# Modulo_de_expansao.net
KiCad netlist of a schematic drawn in EAGLE
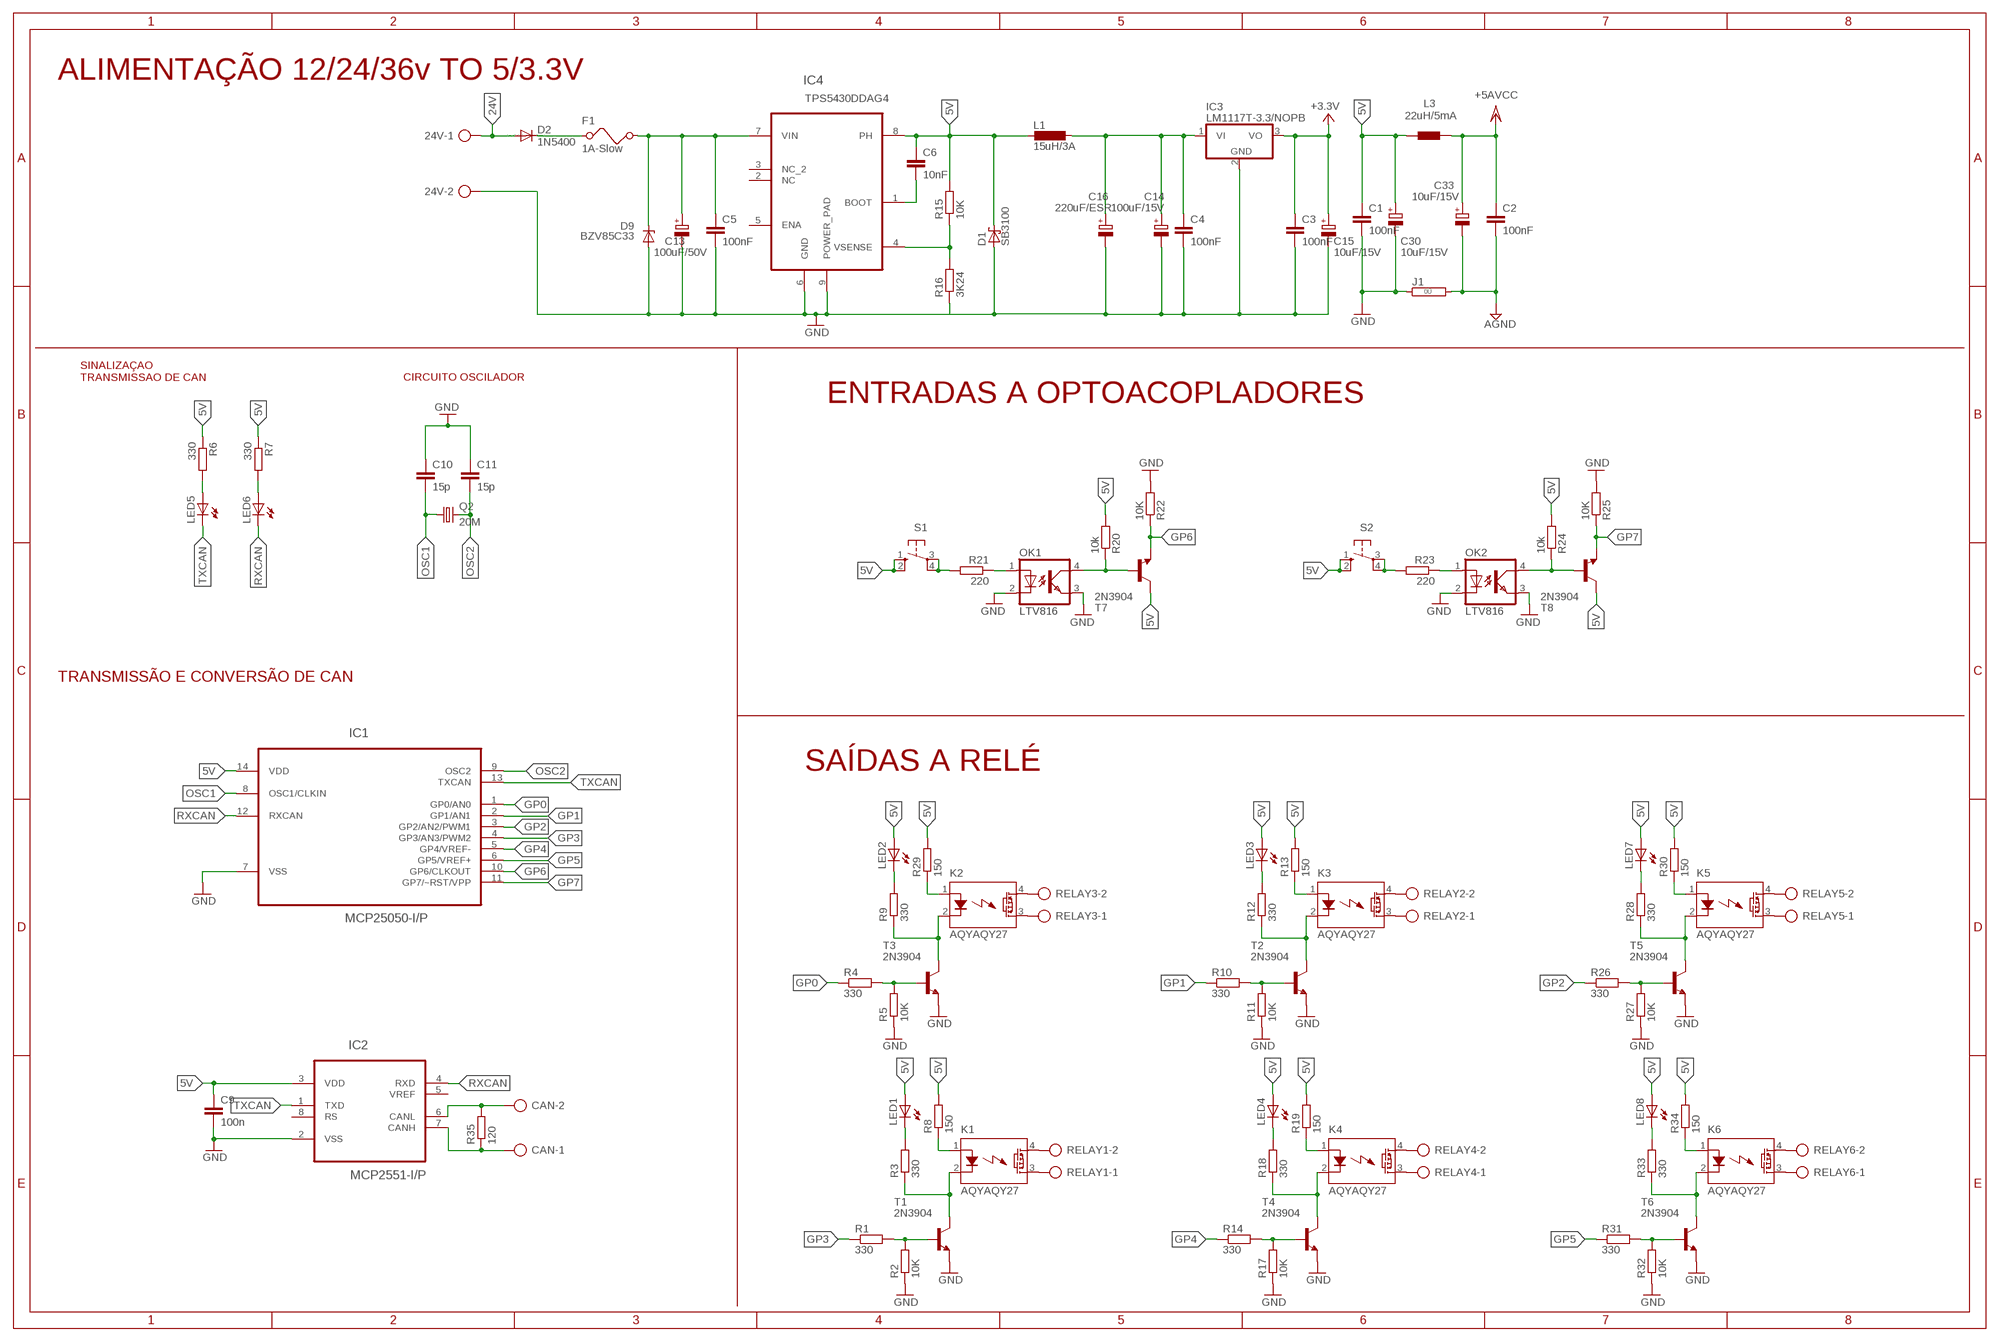
[diagram p0: schematic, sheet 1]

(export (version "E")
  (design (tool "Eeschema 10.0.6"))
  (components
    (comp (ref "24V")
      (value "AK300/2")
      (footprint "eagle-import:AK300_2")
      (libsource (lib "eagle-import") (part "AK300/2"))
    )
    (comp (ref "C1")
      (value "100nF")
      (footprint "eagle-import:C050-024X044")
      (libsource (lib "eagle-import") (part "C-EU050-024X044"))
    )
    (comp (ref "C2")
      (value "100nF")
      (footprint "eagle-import:C050-024X044")
      (libsource (lib "eagle-import") (part "C-EU050-024X044"))
    )
    (comp (ref "C3")
      (value "100nF")
      (footprint "eagle-import:C050-024X044")
      (libsource (lib "eagle-import") (part "C-EU050-024X044"))
    )
    (comp (ref "C4")
      (value "100nF")
      (footprint "eagle-import:C050-024X044")
      (libsource (lib "eagle-import") (part "C-EU050-024X044"))
    )
    (comp (ref "C5")
      (value "100nF")
      (footprint "eagle-import:C050-024X044")
      (libsource (lib "eagle-import") (part "C-EU050-024X044"))
    )
    (comp (ref "C6")
      (value "10nF")
      (footprint "eagle-import:C075-032X103")
      (libsource (lib "eagle-import") (part "C-EU075-032X103"))
    )
    (comp (ref "C9")
      (value "100n")
      (footprint "eagle-import:C050-025X075")
      (libsource (lib "eagle-import") (part "C-EU050-025X075"))
    )
    (comp (ref "C10")
      (value "15p")
      (footprint "eagle-import:C025-024X044")
      (libsource (lib "eagle-import") (part "C-EU025-024X044"))
    )
    (comp (ref "C11")
      (value "15p")
      (footprint "eagle-import:C025-024X044")
      (libsource (lib "eagle-import") (part "C-EU025-024X044"))
    )
    (comp (ref "C13")
      (value "100uF/50V")
      (footprint "eagle-import:E5-10,5")
      (libsource (lib "eagle-import") (part "CPOL-EUE5-10.5"))
    )
    (comp (ref "C14")
      (value "100uF/15V")
      (footprint "eagle-import:E5-10,5")
      (libsource (lib "eagle-import") (part "CPOL-EUE5-10.5"))
    )
    (comp (ref "C15")
      (value "10uF/15V")
      (footprint "eagle-import:E5-10,5")
      (libsource (lib "eagle-import") (part "CPOL-EUE5-10.5"))
    )
    (comp (ref "C16")
      (value "220uF/ESR")
      (footprint "eagle-import:E5-10,5")
      (libsource (lib "eagle-import") (part "CPOL-EUE5-10.5"))
    )
    (comp (ref "C30")
      (value "10uF/15V")
      (footprint "eagle-import:E5-10,5")
      (libsource (lib "eagle-import") (part "CPOL-EUE5-10.5"))
    )
    (comp (ref "C33")
      (value "10uF/15V")
      (footprint "eagle-import:E5-10,5")
      (libsource (lib "eagle-import") (part "CPOL-EUE5-10.5"))
    )
    (comp (ref "CAN")
      (value "AK300/2")
      (footprint "eagle-import:AK300_2")
      (libsource (lib "eagle-import") (part "AK300/2"))
    )
    (comp (ref "D1")
      (value "SB3100")
      (footprint "eagle-import:C4111-15")
      (libsource (lib "eagle-import") (part "1N5908"))
    )
    (comp (ref "D2")
      (value "1N5400")
      (footprint "eagle-import:DO201-15")
      (libsource (lib "eagle-import") (part "1N5400"))
    )
    (comp (ref "D9")
      (value "BZV85C33")
      (footprint "eagle-import:F126Z10")
      (libsource (lib "eagle-import") (part "ZENER-DIODEF126-10"))
    )
    (comp (ref "F1")
      (value "1A-Slow")
      (footprint "eagle-import:FUSE")
      (libsource (lib "eagle-import") (part "FUSE"))
    )
    (comp (ref "IC1")
      (value "MCP25050-I/P")
      (footprint "eagle-import:DIP254P762X432-14")
      (libsource (lib "eagle-import") (part "MCP25050-I/P"))
    )
    (comp (ref "IC2")
      (value "MCP2551-I/P")
      (footprint "eagle-import:DIP254P762X432-8")
      (libsource (lib "eagle-import") (part "MCP2551-I/P"))
    )
    (comp (ref "IC3")
      (value "LM1117T-3.3/NOPB")
      (footprint "eagle-import:TO220H")
      (libsource (lib "eagle-import") (part "LM340?-H12"))
    )
    (comp (ref "IC4")
      (value "TPS5430DDAG4")
      (footprint "eagle-import:SOIC127P600X170-9N")
      (fields (field (name "MPN") "TPS5430DDAG4"))
      (libsource (lib "eagle-import") (part "TPS5430DDAG4"))
    )
    (comp (ref "J1")
      (value "0R")
      (footprint "eagle-import:0R_10")
      (libsource (lib "eagle-import") (part "0R"))
    )
    (comp (ref "K1")
      (value "AQYAQY27")
      (footprint "eagle-import:AQY27")
      (libsource (lib "eagle-import") (part "AQYAQY27"))
    )
    (comp (ref "K2")
      (value "AQYAQY27")
      (footprint "eagle-import:AQY27")
      (libsource (lib "eagle-import") (part "AQYAQY27"))
    )
    (comp (ref "K3")
      (value "AQYAQY27")
      (footprint "eagle-import:AQY27")
      (libsource (lib "eagle-import") (part "AQYAQY27"))
    )
    (comp (ref "K4")
      (value "AQYAQY27")
      (footprint "eagle-import:AQY27")
      (libsource (lib "eagle-import") (part "AQYAQY27"))
    )
    (comp (ref "K5")
      (value "AQYAQY27")
      (footprint "eagle-import:AQY27")
      (libsource (lib "eagle-import") (part "AQYAQY27"))
    )
    (comp (ref "K6")
      (value "AQYAQY27")
      (footprint "eagle-import:AQY27")
      (libsource (lib "eagle-import") (part "AQYAQY27"))
    )
    (comp (ref "L1")
      (value "15uH/3A")
      (footprint "eagle-import:TJ3-U1")
      (libsource (lib "eagle-import") (part "L-EUTJ3-U1"))
    )
    (comp (ref "L3")
      (value "22uH/5mA")
      (footprint "eagle-import:BL01RN1A")
      (libsource (lib "eagle-import") (part "BL01RN1A"))
    )
    (comp (ref "LED1")
      (value "LED3MM")
      (footprint "eagle-import:LED3MM")
      (libsource (lib "eagle-import") (part "LED3MM"))
    )
    (comp (ref "LED2")
      (value "LED3MM")
      (footprint "eagle-import:LED3MM")
      (libsource (lib "eagle-import") (part "LED3MM"))
    )
    (comp (ref "LED3")
      (value "LED3MM")
      (footprint "eagle-import:LED3MM")
      (libsource (lib "eagle-import") (part "LED3MM"))
    )
    (comp (ref "LED4")
      (value "LED3MM")
      (footprint "eagle-import:LED3MM")
      (libsource (lib "eagle-import") (part "LED3MM"))
    )
    (comp (ref "LED5")
      (value "LED3MM")
      (footprint "eagle-import:LED3MM")
      (libsource (lib "eagle-import") (part "LED3MM"))
    )
    (comp (ref "LED6")
      (value "LED3MM")
      (footprint "eagle-import:LED3MM")
      (libsource (lib "eagle-import") (part "LED3MM"))
    )
    (comp (ref "LED7")
      (value "LED3MM")
      (footprint "eagle-import:LED3MM")
      (libsource (lib "eagle-import") (part "LED3MM"))
    )
    (comp (ref "LED8")
      (value "LED3MM")
      (footprint "eagle-import:LED3MM")
      (libsource (lib "eagle-import") (part "LED3MM"))
    )
    (comp (ref "OK1")
      (value "LTV816")
      (footprint "eagle-import:DIL04")
      (libsource (lib "eagle-import") (part "LTV816"))
    )
    (comp (ref "OK2")
      (value "LTV816")
      (footprint "eagle-import:DIL04")
      (libsource (lib "eagle-import") (part "LTV816"))
    )
    (comp (ref "Q2")
      (value "20M")
      (footprint "eagle-import:HC49_S")
      (libsource (lib "eagle-import") (part "CRYSTALHC49S"))
    )
    (comp (ref "R1")
      (value "330")
      (footprint "eagle-import:0204_5")
      (libsource (lib "eagle-import") (part "R-EU_0204/5"))
    )
    (comp (ref "R2")
      (value "10K")
      (footprint "eagle-import:0204_5")
      (libsource (lib "eagle-import") (part "R-EU_0204/5"))
    )
    (comp (ref "R3")
      (value "330")
      (footprint "eagle-import:0204_5")
      (libsource (lib "eagle-import") (part "R-EU_0204/5"))
    )
    (comp (ref "R4")
      (value "330")
      (footprint "eagle-import:0204_5")
      (libsource (lib "eagle-import") (part "R-EU_0204/5"))
    )
    (comp (ref "R5")
      (value "10K")
      (footprint "eagle-import:0204_5")
      (libsource (lib "eagle-import") (part "R-EU_0204/5"))
    )
    (comp (ref "R6")
      (value "330")
      (footprint "eagle-import:0204_5")
      (libsource (lib "eagle-import") (part "R-EU_0204/5"))
    )
    (comp (ref "R7")
      (value "330")
      (footprint "eagle-import:0204_5")
      (libsource (lib "eagle-import") (part "R-EU_0204/5"))
    )
    (comp (ref "R8")
      (value "150")
      (footprint "eagle-import:0204_5")
      (libsource (lib "eagle-import") (part "R-EU_0204/5"))
    )
    (comp (ref "R9")
      (value "330")
      (footprint "eagle-import:0204_5")
      (libsource (lib "eagle-import") (part "R-EU_0204/5"))
    )
    (comp (ref "R10")
      (value "330")
      (footprint "eagle-import:0204_5")
      (libsource (lib "eagle-import") (part "R-EU_0204/5"))
    )
    (comp (ref "R11")
      (value "10K")
      (footprint "eagle-import:0204_5")
      (libsource (lib "eagle-import") (part "R-EU_0204/5"))
    )
    (comp (ref "R12")
      (value "330")
      (footprint "eagle-import:0204_5")
      (libsource (lib "eagle-import") (part "R-EU_0204/5"))
    )
    (comp (ref "R13")
      (value "150")
      (footprint "eagle-import:0204_5")
      (libsource (lib "eagle-import") (part "R-EU_0204/5"))
    )
    (comp (ref "R14")
      (value "330")
      (footprint "eagle-import:0204_5")
      (libsource (lib "eagle-import") (part "R-EU_0204/5"))
    )
    (comp (ref "R15")
      (value "10K")
      (footprint "eagle-import:0204_7")
      (libsource (lib "eagle-import") (part "R-EU_0204/7"))
    )
    (comp (ref "R16")
      (value "3K24")
      (footprint "eagle-import:0204_7")
      (libsource (lib "eagle-import") (part "R-EU_0204/7"))
    )
    (comp (ref "R17")
      (value "10K")
      (footprint "eagle-import:0204_5")
      (libsource (lib "eagle-import") (part "R-EU_0204/5"))
    )
    (comp (ref "R18")
      (value "330")
      (footprint "eagle-import:0204_5")
      (libsource (lib "eagle-import") (part "R-EU_0204/5"))
    )
    (comp (ref "R19")
      (value "150")
      (footprint "eagle-import:0204_5")
      (libsource (lib "eagle-import") (part "R-EU_0204/5"))
    )
    (comp (ref "R20")
      (value "10k")
      (footprint "eagle-import:0204_5")
      (libsource (lib "eagle-import") (part "R-EU_0204/5"))
    )
    (comp (ref "R21")
      (value "220")
      (footprint "eagle-import:0204_5")
      (libsource (lib "eagle-import") (part "R-EU_0204/5"))
    )
    (comp (ref "R22")
      (value "10K")
      (footprint "eagle-import:0204_5")
      (libsource (lib "eagle-import") (part "R-EU_0204/5"))
    )
    (comp (ref "R23")
      (value "220")
      (footprint "eagle-import:0204_5")
      (libsource (lib "eagle-import") (part "R-EU_0204/5"))
    )
    (comp (ref "R24")
      (value "10k")
      (footprint "eagle-import:0204_5")
      (libsource (lib "eagle-import") (part "R-EU_0204/5"))
    )
    (comp (ref "R25")
      (value "10K")
      (footprint "eagle-import:0204_5")
      (libsource (lib "eagle-import") (part "R-EU_0204/5"))
    )
    (comp (ref "R26")
      (value "330")
      (footprint "eagle-import:0204_5")
      (libsource (lib "eagle-import") (part "R-EU_0204/5"))
    )
    (comp (ref "R27")
      (value "10K")
      (footprint "eagle-import:0204_5")
      (libsource (lib "eagle-import") (part "R-EU_0204/5"))
    )
    (comp (ref "R28")
      (value "330")
      (footprint "eagle-import:0204_5")
      (libsource (lib "eagle-import") (part "R-EU_0204/5"))
    )
    (comp (ref "R29")
      (value "150")
      (footprint "eagle-import:0204_5")
      (libsource (lib "eagle-import") (part "R-EU_0204/5"))
    )
    (comp (ref "R30")
      (value "150")
      (footprint "eagle-import:0204_5")
      (libsource (lib "eagle-import") (part "R-EU_0204/5"))
    )
    (comp (ref "R31")
      (value "330")
      (footprint "eagle-import:0204_5")
      (libsource (lib "eagle-import") (part "R-EU_0204/5"))
    )
    (comp (ref "R32")
      (value "10K")
      (footprint "eagle-import:0204_5")
      (libsource (lib "eagle-import") (part "R-EU_0204/5"))
    )
    (comp (ref "R33")
      (value "330")
      (footprint "eagle-import:0204_5")
      (libsource (lib "eagle-import") (part "R-EU_0204/5"))
    )
    (comp (ref "R34")
      (value "150")
      (footprint "eagle-import:0204_5")
      (libsource (lib "eagle-import") (part "R-EU_0204/5"))
    )
    (comp (ref "R35")
      (value "120")
      (footprint "eagle-import:0204_5")
      (libsource (lib "eagle-import") (part "R-EU_0204/5"))
    )
    (comp (ref "RELAY1")
      (value "AK300/2")
      (footprint "eagle-import:AK300_2")
      (libsource (lib "eagle-import") (part "AK300/2"))
    )
    (comp (ref "RELAY2")
      (value "AK300/2")
      (footprint "eagle-import:AK300_2")
      (libsource (lib "eagle-import") (part "AK300/2"))
    )
    (comp (ref "RELAY3")
      (value "AK300/2")
      (footprint "eagle-import:AK300_2")
      (libsource (lib "eagle-import") (part "AK300/2"))
    )
    (comp (ref "RELAY4")
      (value "AK300/2")
      (footprint "eagle-import:AK300_2")
      (libsource (lib "eagle-import") (part "AK300/2"))
    )
    (comp (ref "RELAY5")
      (value "AK300/2")
      (footprint "eagle-import:AK300_2")
      (libsource (lib "eagle-import") (part "AK300/2"))
    )
    (comp (ref "RELAY6")
      (value "AK300/2")
      (footprint "eagle-import:AK300_2")
      (libsource (lib "eagle-import") (part "AK300/2"))
    )
    (comp (ref "S1")
      (value "10-XX")
      (footprint "eagle-import:B3F-10XX")
      (fields (field (name "MPN") "B3F-1000"))
      (libsource (lib "eagle-import") (part "10-XX"))
    )
    (comp (ref "S2")
      (value "10-XX")
      (footprint "eagle-import:B3F-10XX")
      (fields (field (name "MPN") "B3F-1000"))
      (libsource (lib "eagle-import") (part "10-XX"))
    )
    (comp (ref "T1")
      (value "2N3904")
      (footprint "eagle-import:TO92")
      (libsource (lib "eagle-import") (part "2N3904"))
    )
    (comp (ref "T2")
      (value "2N3904")
      (footprint "eagle-import:TO92")
      (libsource (lib "eagle-import") (part "2N3904"))
    )
    (comp (ref "T3")
      (value "2N3904")
      (footprint "eagle-import:TO92")
      (libsource (lib "eagle-import") (part "2N3904"))
    )
    (comp (ref "T4")
      (value "2N3904")
      (footprint "eagle-import:TO92")
      (libsource (lib "eagle-import") (part "2N3904"))
    )
    (comp (ref "T5")
      (value "2N3904")
      (footprint "eagle-import:TO92")
      (libsource (lib "eagle-import") (part "2N3904"))
    )
    (comp (ref "T6")
      (value "2N3904")
      (footprint "eagle-import:TO92")
      (libsource (lib "eagle-import") (part "2N3904"))
    )
    (comp (ref "T7")
      (value "2N3904")
      (footprint "eagle-import:TO92")
      (libsource (lib "eagle-import") (part "2N3904"))
    )
    (comp (ref "T8")
      (value "2N3904")
      (footprint "eagle-import:TO92")
      (libsource (lib "eagle-import") (part "2N3904"))
    )
  )
  (nets
    (net (code "1") (name "+3.3V") (class "Default")
      (node (ref "C15") (pin "+") (pinfunction "+_+") (pintype "passive"))
      (node (ref "C3") (pin "1") (pinfunction "1_1") (pintype "passive"))
      (node (ref "IC3") (pin "3") (pinfunction "VO_3") (pintype "passive"))
    )
    (net (code "2") (name "+5AVCC") (class "Default")
      (node (ref "C2") (pin "1") (pinfunction "1_1") (pintype "passive"))
      (node (ref "C33") (pin "+") (pinfunction "+_+") (pintype "passive"))
      (node (ref "L3") (pin "2") (pinfunction "2_2") (pintype "passive"))
    )
    (net (code "3") (name "5V") (class "Default")
      (node (ref "C1") (pin "1") (pinfunction "1_1") (pintype "passive"))
      (node (ref "C30") (pin "+") (pinfunction "+_+") (pintype "passive"))
      (node (ref "C6") (pin "1") (pinfunction "1_1") (pintype "passive"))
      (node (ref "C9") (pin "1") (pinfunction "1_1") (pintype "passive"))
      (node (ref "D1") (pin "C") (pinfunction "C_C") (pintype "passive"))
      (node (ref "IC1") (pin "14") (pinfunction "VDD_14") (pintype "power_in"))
      (node (ref "IC2") (pin "3") (pinfunction "VDD_3") (pintype "power_in"))
      (node (ref "IC4") (pin "8") (pinfunction "PH_8") (pintype "input"))
      (node (ref "K1") (pin "1") (pinfunction "A_1") (pintype "passive"))
      (node (ref "K2") (pin "1") (pinfunction "A_1") (pintype "passive"))
      (node (ref "K3") (pin "1") (pinfunction "A_1") (pintype "passive"))
      (node (ref "K4") (pin "1") (pinfunction "A_1") (pintype "passive"))
      (node (ref "K5") (pin "1") (pinfunction "A_1") (pintype "passive"))
      (node (ref "K6") (pin "1") (pinfunction "A_1") (pintype "passive"))
      (node (ref "L1") (pin "2") (pinfunction "2_2") (pintype "passive"))
      (node (ref "L3") (pin "1") (pinfunction "1_1") (pintype "passive"))
      (node (ref "LED1") (pin "A") (pinfunction "A_A") (pintype "passive"))
      (node (ref "LED2") (pin "A") (pinfunction "A_A") (pintype "passive"))
      (node (ref "LED3") (pin "A") (pinfunction "A_A") (pintype "passive"))
      (node (ref "LED4") (pin "A") (pinfunction "A_A") (pintype "passive"))
      (node (ref "LED7") (pin "A") (pinfunction "A_A") (pintype "passive"))
      (node (ref "LED8") (pin "A") (pinfunction "A_A") (pintype "passive"))
      (node (ref "R13") (pin "1") (pinfunction "1_1") (pintype "passive"))
      (node (ref "R13") (pin "2") (pinfunction "2_2") (pintype "passive"))
      (node (ref "R15") (pin "2") (pinfunction "2_2") (pintype "passive"))
      (node (ref "R19") (pin "1") (pinfunction "1_1") (pintype "passive"))
      (node (ref "R19") (pin "2") (pinfunction "2_2") (pintype "passive"))
      (node (ref "R20") (pin "2") (pinfunction "2_2") (pintype "passive"))
      (node (ref "R24") (pin "2") (pinfunction "2_2") (pintype "passive"))
      (node (ref "R29") (pin "1") (pinfunction "1_1") (pintype "passive"))
      (node (ref "R29") (pin "2") (pinfunction "2_2") (pintype "passive"))
      (node (ref "R30") (pin "1") (pinfunction "1_1") (pintype "passive"))
      (node (ref "R30") (pin "2") (pinfunction "2_2") (pintype "passive"))
      (node (ref "R34") (pin "1") (pinfunction "1_1") (pintype "passive"))
      (node (ref "R34") (pin "2") (pinfunction "2_2") (pintype "passive"))
      (node (ref "R6") (pin "1") (pinfunction "1_1") (pintype "passive"))
      (node (ref "R7") (pin "1") (pinfunction "1_1") (pintype "passive"))
      (node (ref "R8") (pin "1") (pinfunction "1_1") (pintype "passive"))
      (node (ref "R8") (pin "2") (pinfunction "2_2") (pintype "passive"))
      (node (ref "S1") (pin "1") (pinfunction "S_1") (pintype "passive"))
      (node (ref "S1") (pin "2") (pinfunction "S1_2") (pintype "passive"))
      (node (ref "S2") (pin "1") (pinfunction "S_1") (pintype "passive"))
      (node (ref "S2") (pin "2") (pinfunction "S1_2") (pintype "passive"))
      (node (ref "T7") (pin "1") (pinfunction "C_1") (pintype "passive"))
      (node (ref "T8") (pin "1") (pinfunction "C_1") (pintype "passive"))
    )
    (net (code "4") (name "24V") (class "Default")
      (node (ref "24V") (pin "1") (pinfunction "KL_1") (pintype "passive"))
      (node (ref "D2") (pin "A") (pinfunction "A_A") (pintype "passive"))
    )
    (net (code "5") (name "AGND") (class "Default")
      (node (ref "C2") (pin "2") (pinfunction "2_2") (pintype "passive"))
      (node (ref "C33") (pin "-") (pinfunction "-_-") (pintype "passive"))
      (node (ref "J1") (pin "2") (pinfunction "2_2") (pintype "passive"))
    )
    (net (code "6") (name "GND") (class "Default")
      (node (ref "24V") (pin "2") (pinfunction "KL_2") (pintype "passive"))
      (node (ref "C1") (pin "2") (pinfunction "2_2") (pintype "passive"))
      (node (ref "C10") (pin "1") (pinfunction "1_1") (pintype "passive"))
      (node (ref "C11") (pin "1") (pinfunction "1_1") (pintype "passive"))
      (node (ref "C13") (pin "-") (pinfunction "-_-") (pintype "passive"))
      (node (ref "C14") (pin "-") (pinfunction "-_-") (pintype "passive"))
      (node (ref "C15") (pin "-") (pinfunction "-_-") (pintype "passive"))
      (node (ref "C16") (pin "-") (pinfunction "-_-") (pintype "passive"))
      (node (ref "C3") (pin "2") (pinfunction "2_2") (pintype "passive"))
      (node (ref "C30") (pin "-") (pinfunction "-_-") (pintype "passive"))
      (node (ref "C4") (pin "2") (pinfunction "2_2") (pintype "passive"))
      (node (ref "C5") (pin "2") (pinfunction "2_2") (pintype "passive"))
      (node (ref "C9") (pin "2") (pinfunction "2_2") (pintype "passive"))
      (node (ref "D1") (pin "A") (pinfunction "A_A") (pintype "passive"))
      (node (ref "D9") (pin "A") (pinfunction "A_A") (pintype "passive"))
      (node (ref "IC1") (pin "7") (pinfunction "VSS_7") (pintype "passive"))
      (node (ref "IC2") (pin "2") (pinfunction "VSS_2") (pintype "power_in"))
      (node (ref "IC3") (pin "2") (pinfunction "GND_2") (pintype "passive"))
      (node (ref "IC4") (pin "6") (pinfunction "GND_6") (pintype "passive"))
      (node (ref "IC4") (pin "9") (pinfunction "POWER_PAD_9") (pintype "passive"))
      (node (ref "J1") (pin "1") (pinfunction "1_1") (pintype "passive"))
      (node (ref "OK1") (pin "2") (pinfunction "C_2") (pintype "passive"))
      (node (ref "OK1") (pin "3") (pinfunction "EMIT_3") (pintype "passive"))
      (node (ref "OK2") (pin "2") (pinfunction "C_2") (pintype "passive"))
      (node (ref "OK2") (pin "3") (pinfunction "EMIT_3") (pintype "passive"))
      (node (ref "R11") (pin "1") (pinfunction "1_1") (pintype "passive"))
      (node (ref "R16") (pin "1") (pinfunction "1_1") (pintype "passive"))
      (node (ref "R17") (pin "1") (pinfunction "1_1") (pintype "passive"))
      (node (ref "R2") (pin "1") (pinfunction "1_1") (pintype "passive"))
      (node (ref "R22") (pin "2") (pinfunction "2_2") (pintype "passive"))
      (node (ref "R25") (pin "2") (pinfunction "2_2") (pintype "passive"))
      (node (ref "R27") (pin "1") (pinfunction "1_1") (pintype "passive"))
      (node (ref "R32") (pin "1") (pinfunction "1_1") (pintype "passive"))
      (node (ref "R5") (pin "1") (pinfunction "1_1") (pintype "passive"))
      (node (ref "T1") (pin "3") (pinfunction "E_3") (pintype "passive"))
      (node (ref "T2") (pin "3") (pinfunction "E_3") (pintype "passive"))
      (node (ref "T3") (pin "3") (pinfunction "E_3") (pintype "passive"))
      (node (ref "T4") (pin "3") (pinfunction "E_3") (pintype "passive"))
      (node (ref "T5") (pin "3") (pinfunction "E_3") (pintype "passive"))
      (node (ref "T6") (pin "3") (pinfunction "E_3") (pintype "passive"))
    )
    (net (code "7") (name "GP0") (class "Default")
      (node (ref "IC1") (pin "1") (pinfunction "GP0/AN0_1") (pintype "bidirectional"))
      (node (ref "R4") (pin "1") (pinfunction "1_1") (pintype "passive"))
    )
    (net (code "8") (name "GP1") (class "Default")
      (node (ref "IC1") (pin "2") (pinfunction "GP1/AN1_2") (pintype "bidirectional"))
      (node (ref "R10") (pin "1") (pinfunction "1_1") (pintype "passive"))
    )
    (net (code "9") (name "GP2") (class "Default")
      (node (ref "IC1") (pin "3") (pinfunction "GP2/AN2/PWM1_3") (pintype "bidirectional"))
      (node (ref "R26") (pin "1") (pinfunction "1_1") (pintype "passive"))
    )
    (net (code "10") (name "GP3") (class "Default")
      (node (ref "IC1") (pin "4") (pinfunction "GP3/AN3/PWM2_4") (pintype "bidirectional"))
      (node (ref "R1") (pin "1") (pinfunction "1_1") (pintype "passive"))
    )
    (net (code "11") (name "GP4") (class "Default")
      (node (ref "IC1") (pin "5") (pinfunction "GP4/VREF-_5") (pintype "bidirectional"))
      (node (ref "R14") (pin "1") (pinfunction "1_1") (pintype "passive"))
    )
    (net (code "12") (name "GP5") (class "Default")
      (node (ref "IC1") (pin "6") (pinfunction "GP5/VREF+_6") (pintype "bidirectional"))
      (node (ref "R31") (pin "1") (pinfunction "1_1") (pintype "passive"))
    )
    (net (code "13") (name "GP6") (class "Default")
      (node (ref "IC1") (pin "10") (pinfunction "GP6/CLKOUT_10") (pintype "bidirectional"))
      (node (ref "R22") (pin "1") (pinfunction "1_1") (pintype "passive"))
      (node (ref "T7") (pin "3") (pinfunction "E_3") (pintype "passive"))
    )
    (net (code "14") (name "GP7") (class "Default")
      (node (ref "IC1") (pin "11") (pinfunction "GP7/~{RST/VPP}_11") (pintype "bidirectional"))
      (node (ref "R25") (pin "1") (pinfunction "1_1") (pintype "passive"))
      (node (ref "T8") (pin "3") (pinfunction "E_3") (pintype "passive"))
    )
    (net (code "15") (name "Net-(CANA-KL)") (class "Default")
      (node (ref "CAN") (pin "1") (pinfunction "KL_1") (pintype "passive"))
      (node (ref "IC2") (pin "7") (pinfunction "CANH_7") (pintype "bidirectional"))
      (node (ref "R35") (pin "1") (pinfunction "1_1") (pintype "passive"))
    )
    (net (code "16") (name "Net-(CANB-KL)") (class "Default")
      (node (ref "CAN") (pin "2") (pinfunction "KL_2") (pintype "passive"))
      (node (ref "IC2") (pin "6") (pinfunction "CANL_6") (pintype "bidirectional"))
      (node (ref "R35") (pin "2") (pinfunction "2_2") (pintype "passive"))
    )
    (net (code "17") (name "Net-(D2-PadC)") (class "Default")
      (node (ref "D2") (pin "C") (pinfunction "C_C") (pintype "passive"))
      (node (ref "F1") (pin "1") (pinfunction "1_1") (pintype "passive"))
    )
    (net (code "18") (name "Net-(IC3-VI)") (class "Default")
      (node (ref "C14") (pin "+") (pinfunction "+_+") (pintype "passive"))
      (node (ref "C16") (pin "+") (pinfunction "+_+") (pintype "passive"))
      (node (ref "C4") (pin "1") (pinfunction "1_1") (pintype "passive"))
      (node (ref "IC3") (pin "1") (pinfunction "VI_1") (pintype "input"))
      (node (ref "L1") (pin "1") (pinfunction "1_1") (pintype "passive"))
    )
    (net (code "19") (name "Net-(IC4-BOOT)") (class "Default")
      (node (ref "C6") (pin "2") (pinfunction "2_2") (pintype "passive"))
      (node (ref "IC4") (pin "1") (pinfunction "BOOT_1") (pintype "passive"))
    )
    (net (code "20") (name "Net-(IC4-VIN)") (class "Default")
      (node (ref "C13") (pin "+") (pinfunction "+_+") (pintype "passive"))
      (node (ref "C5") (pin "1") (pinfunction "1_1") (pintype "passive"))
      (node (ref "D9") (pin "C") (pinfunction "C_C") (pintype "passive"))
      (node (ref "F1") (pin "2") (pinfunction "2_2") (pintype "passive"))
      (node (ref "IC4") (pin "7") (pinfunction "VIN_7") (pintype "power_in"))
    )
    (net (code "21") (name "Net-(IC4-VSENSE)") (class "Default")
      (node (ref "IC4") (pin "4") (pinfunction "VSENSE_4") (pintype "output"))
      (node (ref "R15") (pin "1") (pinfunction "1_1") (pintype "passive"))
      (node (ref "R16") (pin "2") (pinfunction "2_2") (pintype "passive"))
    )
    (net (code "22") (name "Net-(K1-DS1)") (class "Default")
      (node (ref "K1") (pin "4") (pinfunction "DS1_4") (pintype "passive"))
      (node (ref "RELAY1") (pin "2") (pinfunction "KL_2") (pintype "passive"))
    )
    (net (code "23") (name "Net-(K1-DS2)") (class "Default")
      (node (ref "K1") (pin "3") (pinfunction "DS2_3") (pintype "passive"))
      (node (ref "RELAY1") (pin "1") (pinfunction "KL_1") (pintype "passive"))
    )
    (net (code "24") (name "Net-(K1-K)") (class "Default")
      (node (ref "K1") (pin "2") (pinfunction "K_2") (pintype "passive"))
      (node (ref "R3") (pin "1") (pinfunction "1_1") (pintype "passive"))
      (node (ref "T1") (pin "1") (pinfunction "C_1") (pintype "passive"))
    )
    (net (code "25") (name "Net-(K2-DS1)") (class "Default")
      (node (ref "K2") (pin "4") (pinfunction "DS1_4") (pintype "passive"))
      (node (ref "RELAY3") (pin "2") (pinfunction "KL_2") (pintype "passive"))
    )
    (net (code "26") (name "Net-(K2-DS2)") (class "Default")
      (node (ref "K2") (pin "3") (pinfunction "DS2_3") (pintype "passive"))
      (node (ref "RELAY3") (pin "1") (pinfunction "KL_1") (pintype "passive"))
    )
    (net (code "27") (name "Net-(K2-K)") (class "Default")
      (node (ref "K2") (pin "2") (pinfunction "K_2") (pintype "passive"))
      (node (ref "R9") (pin "1") (pinfunction "1_1") (pintype "passive"))
      (node (ref "T3") (pin "1") (pinfunction "C_1") (pintype "passive"))
    )
    (net (code "28") (name "Net-(K3-DS1)") (class "Default")
      (node (ref "K3") (pin "4") (pinfunction "DS1_4") (pintype "passive"))
      (node (ref "RELAY2") (pin "2") (pinfunction "KL_2") (pintype "passive"))
    )
    (net (code "29") (name "Net-(K3-DS2)") (class "Default")
      (node (ref "K3") (pin "3") (pinfunction "DS2_3") (pintype "passive"))
      (node (ref "RELAY2") (pin "1") (pinfunction "KL_1") (pintype "passive"))
    )
    (net (code "30") (name "Net-(K3-K)") (class "Default")
      (node (ref "K3") (pin "2") (pinfunction "K_2") (pintype "passive"))
      (node (ref "R12") (pin "1") (pinfunction "1_1") (pintype "passive"))
      (node (ref "T2") (pin "1") (pinfunction "C_1") (pintype "passive"))
    )
    (net (code "31") (name "Net-(K4-DS1)") (class "Default")
      (node (ref "K4") (pin "4") (pinfunction "DS1_4") (pintype "passive"))
      (node (ref "RELAY4") (pin "2") (pinfunction "KL_2") (pintype "passive"))
    )
    (net (code "32") (name "Net-(K4-DS2)") (class "Default")
      (node (ref "K4") (pin "3") (pinfunction "DS2_3") (pintype "passive"))
      (node (ref "RELAY4") (pin "1") (pinfunction "KL_1") (pintype "passive"))
    )
    (net (code "33") (name "Net-(K4-K)") (class "Default")
      (node (ref "K4") (pin "2") (pinfunction "K_2") (pintype "passive"))
      (node (ref "R18") (pin "1") (pinfunction "1_1") (pintype "passive"))
      (node (ref "T4") (pin "1") (pinfunction "C_1") (pintype "passive"))
    )
    (net (code "34") (name "Net-(K5-DS1)") (class "Default")
      (node (ref "K5") (pin "4") (pinfunction "DS1_4") (pintype "passive"))
      (node (ref "RELAY5") (pin "2") (pinfunction "KL_2") (pintype "passive"))
    )
    (net (code "35") (name "Net-(K5-DS2)") (class "Default")
      (node (ref "K5") (pin "3") (pinfunction "DS2_3") (pintype "passive"))
      (node (ref "RELAY5") (pin "1") (pinfunction "KL_1") (pintype "passive"))
    )
    (net (code "36") (name "Net-(K5-K)") (class "Default")
      (node (ref "K5") (pin "2") (pinfunction "K_2") (pintype "passive"))
      (node (ref "R28") (pin "1") (pinfunction "1_1") (pintype "passive"))
      (node (ref "T5") (pin "1") (pinfunction "C_1") (pintype "passive"))
    )
    (net (code "37") (name "Net-(K6-DS1)") (class "Default")
      (node (ref "K6") (pin "4") (pinfunction "DS1_4") (pintype "passive"))
      (node (ref "RELAY6") (pin "2") (pinfunction "KL_2") (pintype "passive"))
    )
    (net (code "38") (name "Net-(K6-DS2)") (class "Default")
      (node (ref "K6") (pin "3") (pinfunction "DS2_3") (pintype "passive"))
      (node (ref "RELAY6") (pin "1") (pinfunction "KL_1") (pintype "passive"))
    )
    (net (code "39") (name "Net-(K6-K)") (class "Default")
      (node (ref "K6") (pin "2") (pinfunction "K_2") (pintype "passive"))
      (node (ref "R33") (pin "1") (pinfunction "1_1") (pintype "passive"))
      (node (ref "T6") (pin "1") (pinfunction "C_1") (pintype "passive"))
    )
    (net (code "40") (name "Net-(LED1-C)") (class "Default")
      (node (ref "LED1") (pin "K") (pinfunction "C_K") (pintype "passive"))
      (node (ref "R3") (pin "2") (pinfunction "2_2") (pintype "passive"))
    )
    (net (code "41") (name "Net-(LED2-C)") (class "Default")
      (node (ref "LED2") (pin "K") (pinfunction "C_K") (pintype "passive"))
      (node (ref "R9") (pin "2") (pinfunction "2_2") (pintype "passive"))
    )
    (net (code "42") (name "Net-(LED3-C)") (class "Default")
      (node (ref "LED3") (pin "K") (pinfunction "C_K") (pintype "passive"))
      (node (ref "R12") (pin "2") (pinfunction "2_2") (pintype "passive"))
    )
    (net (code "43") (name "Net-(LED4-C)") (class "Default")
      (node (ref "LED4") (pin "K") (pinfunction "C_K") (pintype "passive"))
      (node (ref "R18") (pin "2") (pinfunction "2_2") (pintype "passive"))
    )
    (net (code "44") (name "Net-(LED5-PadA)") (class "Default")
      (node (ref "LED5") (pin "A") (pinfunction "A_A") (pintype "passive"))
      (node (ref "R6") (pin "2") (pinfunction "2_2") (pintype "passive"))
    )
    (net (code "45") (name "Net-(LED6-PadA)") (class "Default")
      (node (ref "LED6") (pin "A") (pinfunction "A_A") (pintype "passive"))
      (node (ref "R7") (pin "2") (pinfunction "2_2") (pintype "passive"))
    )
    (net (code "46") (name "Net-(LED7-C)") (class "Default")
      (node (ref "LED7") (pin "K") (pinfunction "C_K") (pintype "passive"))
      (node (ref "R28") (pin "2") (pinfunction "2_2") (pintype "passive"))
    )
    (net (code "47") (name "Net-(LED8-C)") (class "Default")
      (node (ref "LED8") (pin "K") (pinfunction "C_K") (pintype "passive"))
      (node (ref "R33") (pin "2") (pinfunction "2_2") (pintype "passive"))
    )
    (net (code "48") (name "Net-(OK1-A)") (class "Default")
      (node (ref "OK1") (pin "1") (pinfunction "A_1") (pintype "passive"))
      (node (ref "R21") (pin "1") (pinfunction "1_1") (pintype "passive"))
    )
    (net (code "49") (name "Net-(OK1-COL)") (class "Default")
      (node (ref "OK1") (pin "4") (pinfunction "COL_4") (pintype "passive"))
      (node (ref "R20") (pin "1") (pinfunction "1_1") (pintype "passive"))
      (node (ref "T7") (pin "2") (pinfunction "B_2") (pintype "passive"))
    )
    (net (code "50") (name "Net-(OK2-A)") (class "Default")
      (node (ref "OK2") (pin "1") (pinfunction "A_1") (pintype "passive"))
      (node (ref "R23") (pin "1") (pinfunction "1_1") (pintype "passive"))
    )
    (net (code "51") (name "Net-(OK2-COL)") (class "Default")
      (node (ref "OK2") (pin "4") (pinfunction "COL_4") (pintype "passive"))
      (node (ref "R24") (pin "1") (pinfunction "1_1") (pintype "passive"))
      (node (ref "T8") (pin "2") (pinfunction "B_2") (pintype "passive"))
    )
    (net (code "52") (name "Net-(S1-P)") (class "Default")
      (node (ref "R21") (pin "2") (pinfunction "2_2") (pintype "passive"))
      (node (ref "S1") (pin "3") (pinfunction "P_3") (pintype "passive"))
      (node (ref "S1") (pin "4") (pinfunction "P1_4") (pintype "passive"))
    )
    (net (code "53") (name "Net-(S2-P)") (class "Default")
      (node (ref "R23") (pin "2") (pinfunction "2_2") (pintype "passive"))
      (node (ref "S2") (pin "3") (pinfunction "P_3") (pintype "passive"))
      (node (ref "S2") (pin "4") (pinfunction "P1_4") (pintype "passive"))
    )
    (net (code "54") (name "Net-(T1-B)") (class "Default")
      (node (ref "R1") (pin "2") (pinfunction "2_2") (pintype "passive"))
      (node (ref "R2") (pin "2") (pinfunction "2_2") (pintype "passive"))
      (node (ref "T1") (pin "2") (pinfunction "B_2") (pintype "passive"))
    )
    (net (code "55") (name "Net-(T2-B)") (class "Default")
      (node (ref "R10") (pin "2") (pinfunction "2_2") (pintype "passive"))
      (node (ref "R11") (pin "2") (pinfunction "2_2") (pintype "passive"))
      (node (ref "T2") (pin "2") (pinfunction "B_2") (pintype "passive"))
    )
    (net (code "56") (name "Net-(T3-B)") (class "Default")
      (node (ref "R4") (pin "2") (pinfunction "2_2") (pintype "passive"))
      (node (ref "R5") (pin "2") (pinfunction "2_2") (pintype "passive"))
      (node (ref "T3") (pin "2") (pinfunction "B_2") (pintype "passive"))
    )
    (net (code "57") (name "Net-(T4-B)") (class "Default")
      (node (ref "R14") (pin "2") (pinfunction "2_2") (pintype "passive"))
      (node (ref "R17") (pin "2") (pinfunction "2_2") (pintype "passive"))
      (node (ref "T4") (pin "2") (pinfunction "B_2") (pintype "passive"))
    )
    (net (code "58") (name "Net-(T5-B)") (class "Default")
      (node (ref "R26") (pin "2") (pinfunction "2_2") (pintype "passive"))
      (node (ref "R27") (pin "2") (pinfunction "2_2") (pintype "passive"))
      (node (ref "T5") (pin "2") (pinfunction "B_2") (pintype "passive"))
    )
    (net (code "59") (name "Net-(T6-B)") (class "Default")
      (node (ref "R31") (pin "2") (pinfunction "2_2") (pintype "passive"))
      (node (ref "R32") (pin "2") (pinfunction "2_2") (pintype "passive"))
      (node (ref "T6") (pin "2") (pinfunction "B_2") (pintype "passive"))
    )
    (net (code "60") (name "OSC1") (class "Default")
      (node (ref "C10") (pin "2") (pinfunction "2_2") (pintype "passive"))
      (node (ref "IC1") (pin "8") (pinfunction "OSC1/CLKIN_8") (pintype "input"))
      (node (ref "Q2") (pin "1") (pinfunction "1_1") (pintype "passive"))
    )
    (net (code "61") (name "OSC2") (class "Default")
      (node (ref "C11") (pin "2") (pinfunction "2_2") (pintype "passive"))
      (node (ref "IC1") (pin "9") (pinfunction "OSC2_9") (pintype "output"))
      (node (ref "Q2") (pin "2") (pinfunction "2_2") (pintype "passive"))
    )
    (net (code "62") (name "RXCAN") (class "Default")
      (node (ref "IC1") (pin "12") (pinfunction "RXCAN_12") (pintype "input"))
      (node (ref "IC2") (pin "4") (pinfunction "RXD_4") (pintype "output"))
      (node (ref "LED6") (pin "K") (pinfunction "C_K") (pintype "passive"))
    )
    (net (code "63") (name "TXCAN") (class "Default")
      (node (ref "IC1") (pin "13") (pinfunction "TXCAN_13") (pintype "output"))
      (node (ref "IC2") (pin "1") (pinfunction "TXD_1") (pintype "input"))
      (node (ref "LED5") (pin "K") (pinfunction "C_K") (pintype "passive"))
    )
    (net (code "64") (name "unconnected-(IC2-RS-Pad8)") (class "Default")
      (node (ref "IC2") (pin "8") (pinfunction "RS_8") (pintype "input"))
    )
    (net (code "65") (name "unconnected-(IC2-VREF-Pad5)") (class "Default")
      (node (ref "IC2") (pin "5") (pinfunction "VREF_5") (pintype "output"))
    )
    (net (code "66") (name "unconnected-(IC4-ENA-Pad5)") (class "Default")
      (node (ref "IC4") (pin "5") (pinfunction "ENA_5") (pintype "input"))
    )
    (net (code "67") (name "unconnected-(IC4-NC-Pad2)") (class "Default")
      (node (ref "IC4") (pin "2") (pinfunction "NC_2") (pintype "no_connect"))
    )
    (net (code "68") (name "unconnected-(IC4-NC_2-Pad3)") (class "Default")
      (node (ref "IC4") (pin "3") (pinfunction "NC_2_3") (pintype "no_connect"))
    )
  )
)
